# soth-core.net
KiCad netlist of a schematic drawn in EAGLE
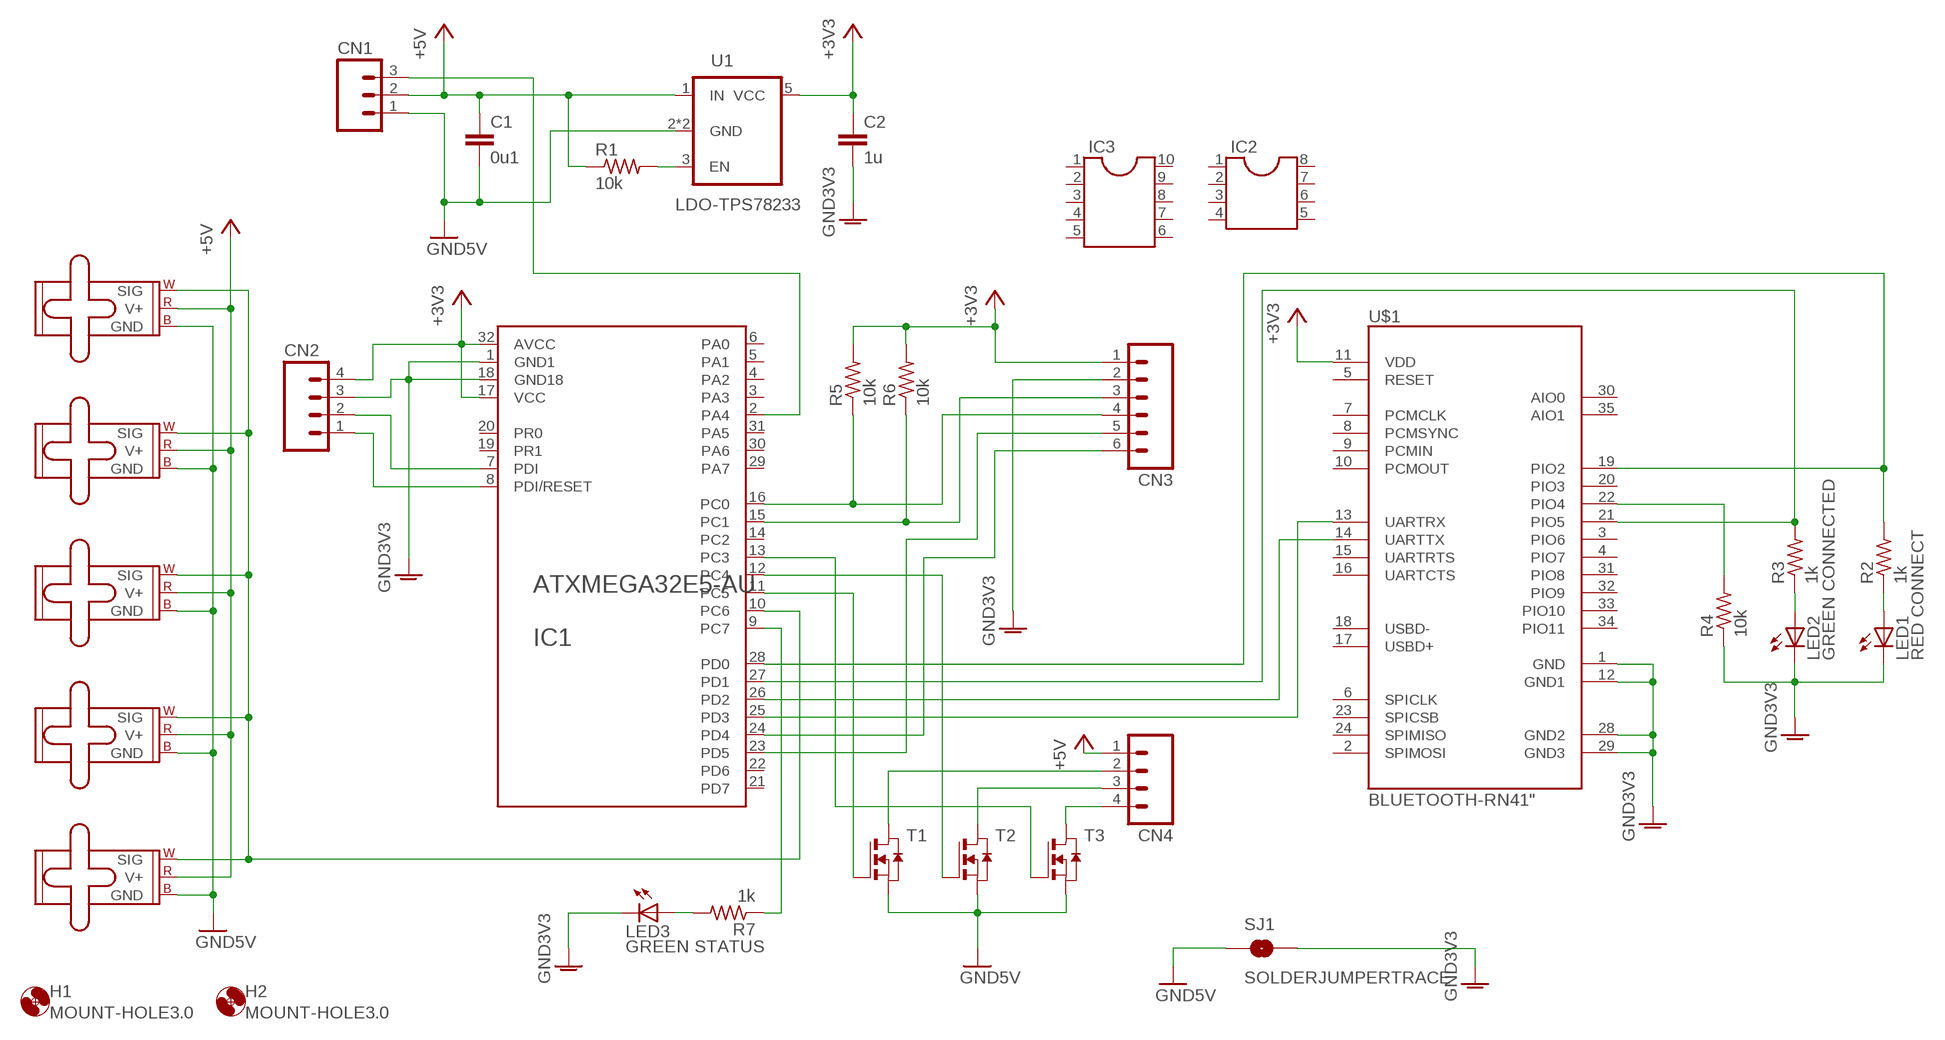
[diagram p0: schematic, sheet 1]

(export (version "E")
  (design (tool "Eeschema 10.0.6"))
  (components
    (comp (ref "C1")
      (value "0u1")
      (footprint "eagle-import:C1608")
      (libsource (lib "eagle-import") (part "C-EUC1608"))
    )
    (comp (ref "C2")
      (value "1u")
      (footprint "eagle-import:C1608")
      (libsource (lib "eagle-import") (part "C-EUC1608"))
    )
    (comp (ref "CN1")
      (value "M03PTH")
      (footprint "eagle-import:1X03")
      (libsource (lib "eagle-import") (part "M03PTH"))
    )
    (comp (ref "CN2")
      (value "M04PTH")
      (footprint "eagle-import:1X04")
      (libsource (lib "eagle-import") (part "M04PTH"))
    )
    (comp (ref "CN3")
      (value "M06SILK_FEMALE_PTH")
      (footprint "eagle-import:1X06")
      (libsource (lib "eagle-import") (part "M06SILK_FEMALE_PTH"))
    )
    (comp (ref "CN4")
      (value "M04PTH")
      (footprint "eagle-import:1X04")
      (libsource (lib "eagle-import") (part "M04PTH"))
    )
    (comp (ref "H1")
      (value "MOUNT-HOLE3.0")
      (footprint "eagle-import:3,0")
      (libsource (lib "eagle-import") (part "MOUNT-HOLE3.0"))
    )
    (comp (ref "H2")
      (value "MOUNT-HOLE3.0")
      (footprint "eagle-import:3,0")
      (libsource (lib "eagle-import") (part "MOUNT-HOLE3.0"))
    )
    (comp (ref "IC1")
      (value "ATXMEGA32E5-AU")
      (footprint "eagle-import:TQFP32-08")
      (libsource (lib "eagle-import") (part "ATXMEGA32E5/16E5/8E5ATXMEGA32E5-AU"))
    )
    (comp (ref "IC2")
      (value "DIL8")
      (footprint "eagle-import:DIL08")
      (libsource (lib "eagle-import") (part "DIL8"))
    )
    (comp (ref "IC3")
      (value "DIL10")
      (footprint "eagle-import:DIL10")
      (libsource (lib "eagle-import") (part "DIL10"))
    )
    (comp (ref "LED1")
      (value "RED CONNECT")
      (footprint "eagle-import:CHIPLED_1206")
      (libsource (lib "eagle-import") (part "LEDCHIPLED_1206"))
    )
    (comp (ref "LED2")
      (value "GREEN CONNECTED")
      (footprint "eagle-import:CHIPLED_1206")
      (libsource (lib "eagle-import") (part "LEDCHIPLED_1206"))
    )
    (comp (ref "LED3")
      (value "GREEN STATUS")
      (footprint "eagle-import:CHIPLED_1206")
      (libsource (lib "eagle-import") (part "LEDCHIPLED_1206"))
    )
    (comp (ref "M1")
      (value "SMALL_SERVO")
      (footprint "eagle-import:1X03")
      (libsource (lib "eagle-import") (part "SMALL_SERVO"))
    )
    (comp (ref "M2")
      (value "SMALL_SERVO")
      (footprint "eagle-import:1X03")
      (libsource (lib "eagle-import") (part "SMALL_SERVO"))
    )
    (comp (ref "M3")
      (value "SMALL_SERVO")
      (footprint "eagle-import:1X03")
      (libsource (lib "eagle-import") (part "SMALL_SERVO"))
    )
    (comp (ref "M4")
      (value "SMALL_SERVO")
      (footprint "eagle-import:1X03")
      (libsource (lib "eagle-import") (part "SMALL_SERVO"))
    )
    (comp (ref "M5")
      (value "SMALL_SERVO")
      (footprint "eagle-import:1X03")
      (libsource (lib "eagle-import") (part "SMALL_SERVO"))
    )
    (comp (ref "R1")
      (value "10k")
      (footprint "eagle-import:R0603")
      (libsource (lib "eagle-import") (part "R-US_R0603"))
    )
    (comp (ref "R2")
      (value "1k")
      (footprint "eagle-import:R0603")
      (libsource (lib "eagle-import") (part "R-US_R0603"))
    )
    (comp (ref "R3")
      (value "1k")
      (footprint "eagle-import:R0603")
      (libsource (lib "eagle-import") (part "R-US_R0603"))
    )
    (comp (ref "R4")
      (value "10k")
      (footprint "eagle-import:R0603")
      (libsource (lib "eagle-import") (part "R-US_R0603"))
    )
    (comp (ref "R5")
      (value "10k")
      (footprint "eagle-import:R0603")
      (libsource (lib "eagle-import") (part "R-US_R0603"))
    )
    (comp (ref "R6")
      (value "10k")
      (footprint "eagle-import:R0603")
      (libsource (lib "eagle-import") (part "R-US_R0603"))
    )
    (comp (ref "R7")
      (value "1k")
      (footprint "eagle-import:R0603")
      (libsource (lib "eagle-import") (part "R-US_R0603"))
    )
    (comp (ref "SJ1")
      (value "SOLDERJUMPERTRACE")
      (footprint "eagle-import:SJ_2S-TRACE")
      (libsource (lib "eagle-import") (part "SOLDERJUMPERTRACE"))
    )
    (comp (ref "T1")
      (value "NMOSSOT23")
      (footprint "eagle-import:SOT-23")
      (libsource (lib "eagle-import") (part "NMOSSOT23"))
    )
    (comp (ref "T2")
      (value "NMOSSOT23")
      (footprint "eagle-import:SOT-23")
      (libsource (lib "eagle-import") (part "NMOSSOT23"))
    )
    (comp (ref "T3")
      (value "NMOSSOT23")
      (footprint "eagle-import:SOT-23")
      (libsource (lib "eagle-import") (part "NMOSSOT23"))
    )
    (comp (ref "U$1")
      (value "BLUETOOTH-RN41\"")
      (footprint "eagle-import:RN41")
      (libsource (lib "eagle-import") (part "BLUETOOTH-RN41{dblquote}"))
    )
    (comp (ref "U1")
      (value "LDO-TPS78233")
      (footprint "eagle-import:SOT23-5")
      (libsource (lib "eagle-import") (part "LDO-TPS78233"))
    )
  )
  (nets
    (net (code "1") (name "+3V3") (class "Default")
      (node (ref "C2") (pin "1") (pinfunction "1_1") (pintype "passive"))
      (node (ref "CN2") (pin "4") (pinfunction "4_4") (pintype "passive"))
      (node (ref "CN3") (pin "1") (pinfunction "1_1") (pintype "passive"))
      (node (ref "IC1") (pin "17") (pinfunction "VCC_17") (pintype "power_in"))
      (node (ref "IC1") (pin "32") (pinfunction "AVCC_32") (pintype "power_in"))
      (node (ref "R5") (pin "2") (pinfunction "2_2") (pintype "passive"))
      (node (ref "R6") (pin "2") (pinfunction "2_2") (pintype "passive"))
      (node (ref "U$1") (pin "11") (pinfunction "VDD_11") (pintype "bidirectional"))
      (node (ref "U1") (pin "5") (pinfunction "VCC_5") (pintype "power_in"))
    )
    (net (code "2") (name "+5V") (class "Default")
      (node (ref "C1") (pin "1") (pinfunction "1_1") (pintype "passive"))
      (node (ref "CN1") (pin "2") (pinfunction "2_2") (pintype "passive"))
      (node (ref "CN4") (pin "1") (pinfunction "1_1") (pintype "passive"))
      (node (ref "M1") (pin "2") (pinfunction "V+_2") (pintype "bidirectional"))
      (node (ref "M2") (pin "2") (pinfunction "V+_2") (pintype "bidirectional"))
      (node (ref "M3") (pin "2") (pinfunction "V+_2") (pintype "bidirectional"))
      (node (ref "M4") (pin "2") (pinfunction "V+_2") (pintype "bidirectional"))
      (node (ref "M5") (pin "2") (pinfunction "V+_2") (pintype "bidirectional"))
      (node (ref "R1") (pin "1") (pinfunction "1_1") (pintype "passive"))
      (node (ref "U1") (pin "1") (pinfunction "IN_1") (pintype "input"))
    )
    (net (code "3") (name "GND3V3") (class "Default")
      (node (ref "C2") (pin "2") (pinfunction "2_2") (pintype "passive"))
      (node (ref "CN2") (pin "3") (pinfunction "3_3") (pintype "passive"))
      (node (ref "CN3") (pin "2") (pinfunction "2_2") (pintype "passive"))
      (node (ref "IC1") (pin "1") (pinfunction "GND1_1") (pintype "power_in"))
      (node (ref "IC1") (pin "18") (pinfunction "GND18_18") (pintype "power_in"))
      (node (ref "LED1") (pin "C") (pinfunction "C_C") (pintype "passive"))
      (node (ref "LED2") (pin "C") (pinfunction "C_C") (pintype "passive"))
      (node (ref "LED3") (pin "C") (pinfunction "C_C") (pintype "passive"))
      (node (ref "R4") (pin "1") (pinfunction "1_1") (pintype "passive"))
      (node (ref "SJ1") (pin "2") (pinfunction "2_2") (pintype "passive"))
      (node (ref "U$1") (pin "1") (pinfunction "GND_1") (pintype "bidirectional"))
      (node (ref "U$1") (pin "12") (pinfunction "GND1_12") (pintype "bidirectional"))
      (node (ref "U$1") (pin "28") (pinfunction "GND2_28") (pintype "bidirectional"))
      (node (ref "U$1") (pin "29") (pinfunction "GND3_29") (pintype "bidirectional"))
    )
    (net (code "4") (name "GND5V") (class "Default")
      (node (ref "C1") (pin "2") (pinfunction "2_2") (pintype "passive"))
      (node (ref "CN1") (pin "1") (pinfunction "1_1") (pintype "passive"))
      (node (ref "M1") (pin "3") (pinfunction "GND_3") (pintype "bidirectional"))
      (node (ref "M2") (pin "3") (pinfunction "GND_3") (pintype "bidirectional"))
      (node (ref "M3") (pin "3") (pinfunction "GND_3") (pintype "bidirectional"))
      (node (ref "M4") (pin "3") (pinfunction "GND_3") (pintype "bidirectional"))
      (node (ref "M5") (pin "3") (pinfunction "GND_3") (pintype "bidirectional"))
      (node (ref "SJ1") (pin "1") (pinfunction "1_1") (pintype "passive"))
      (node (ref "T1") (pin "2") (pinfunction "S_2") (pintype "passive"))
      (node (ref "T2") (pin "2") (pinfunction "S_2") (pintype "passive"))
      (node (ref "T3") (pin "2") (pinfunction "S_2") (pintype "passive"))
      (node (ref "U1") (pin "2") (pinfunction "GND_2") (pintype "input"))
      (node (ref "U1") (pin "4") (pinfunction "GND_4") (pintype "input"))
    )
    (net (code "5") (name "Net-(IC1-PA4)") (class "Default")
      (node (ref "CN1") (pin "3") (pinfunction "3_3") (pintype "passive"))
      (node (ref "IC1") (pin "2") (pinfunction "PA4_2") (pintype "bidirectional"))
    )
    (net (code "6") (name "Net-(IC1-PC0)") (class "Default")
      (node (ref "CN3") (pin "4") (pinfunction "4_4") (pintype "passive"))
      (node (ref "IC1") (pin "16") (pinfunction "PC0_16") (pintype "bidirectional"))
      (node (ref "R5") (pin "1") (pinfunction "1_1") (pintype "passive"))
    )
    (net (code "7") (name "Net-(IC1-PC1)") (class "Default")
      (node (ref "CN3") (pin "3") (pinfunction "3_3") (pintype "passive"))
      (node (ref "IC1") (pin "15") (pinfunction "PC1_15") (pintype "bidirectional"))
      (node (ref "R6") (pin "1") (pinfunction "1_1") (pintype "passive"))
    )
    (net (code "8") (name "Net-(IC1-PC3)") (class "Default")
      (node (ref "IC1") (pin "13") (pinfunction "PC3_13") (pintype "bidirectional"))
      (node (ref "T3") (pin "3") (pinfunction "G_3") (pintype "passive"))
    )
    (net (code "9") (name "Net-(IC1-PC4)") (class "Default")
      (node (ref "IC1") (pin "12") (pinfunction "PC4_12") (pintype "bidirectional"))
      (node (ref "T2") (pin "3") (pinfunction "G_3") (pintype "passive"))
    )
    (net (code "10") (name "Net-(IC1-PC5)") (class "Default")
      (node (ref "IC1") (pin "11") (pinfunction "PC5_11") (pintype "bidirectional"))
      (node (ref "T1") (pin "3") (pinfunction "G_3") (pintype "passive"))
    )
    (net (code "11") (name "Net-(IC1-PC6)") (class "Default")
      (node (ref "IC1") (pin "10") (pinfunction "PC6_10") (pintype "bidirectional"))
      (node (ref "M1") (pin "1") (pinfunction "SIG_1") (pintype "bidirectional"))
      (node (ref "M2") (pin "1") (pinfunction "SIG_1") (pintype "bidirectional"))
      (node (ref "M3") (pin "1") (pinfunction "SIG_1") (pintype "bidirectional"))
      (node (ref "M4") (pin "1") (pinfunction "SIG_1") (pintype "bidirectional"))
      (node (ref "M5") (pin "1") (pinfunction "SIG_1") (pintype "bidirectional"))
    )
    (net (code "12") (name "Net-(IC1-PC7)") (class "Default")
      (node (ref "IC1") (pin "9") (pinfunction "PC7_9") (pintype "bidirectional"))
      (node (ref "R7") (pin "1") (pinfunction "1_1") (pintype "passive"))
    )
    (net (code "13") (name "Net-(IC1-PD0)") (class "Default")
      (node (ref "IC1") (pin "28") (pinfunction "PD0_28") (pintype "bidirectional"))
      (node (ref "R2") (pin "2") (pinfunction "2_2") (pintype "passive"))
      (node (ref "U$1") (pin "19") (pinfunction "PIO2_19") (pintype "bidirectional"))
    )
    (net (code "14") (name "Net-(IC1-PD1)") (class "Default")
      (node (ref "IC1") (pin "27") (pinfunction "PD1_27") (pintype "bidirectional"))
      (node (ref "R3") (pin "2") (pinfunction "2_2") (pintype "passive"))
      (node (ref "U$1") (pin "21") (pinfunction "PIO5_21") (pintype "bidirectional"))
    )
    (net (code "15") (name "Net-(IC1-PD2)") (class "Default")
      (node (ref "IC1") (pin "26") (pinfunction "PD2_26") (pintype "bidirectional"))
      (node (ref "U$1") (pin "14") (pinfunction "UARTTX_14") (pintype "bidirectional"))
    )
    (net (code "16") (name "Net-(IC1-PD3)") (class "Default")
      (node (ref "IC1") (pin "25") (pinfunction "PD3_25") (pintype "bidirectional"))
      (node (ref "U$1") (pin "13") (pinfunction "UARTRX_13") (pintype "bidirectional"))
    )
    (net (code "17") (name "Net-(IC1-PD4)") (class "Default")
      (node (ref "CN3") (pin "6") (pinfunction "6_6") (pintype "passive"))
      (node (ref "IC1") (pin "24") (pinfunction "PD4_24") (pintype "bidirectional"))
    )
    (net (code "18") (name "Net-(IC1-PD5)") (class "Default")
      (node (ref "CN3") (pin "5") (pinfunction "5_5") (pintype "passive"))
      (node (ref "IC1") (pin "23") (pinfunction "PD5_23") (pintype "bidirectional"))
    )
    (net (code "19") (name "Net-(IC1-PDI)") (class "Default")
      (node (ref "CN2") (pin "2") (pinfunction "2_2") (pintype "passive"))
      (node (ref "IC1") (pin "7") (pinfunction "PDI_7") (pintype "bidirectional"))
    )
    (net (code "20") (name "Net-(IC1-PDI{slash}RESET)") (class "Default")
      (node (ref "CN2") (pin "1") (pinfunction "1_1") (pintype "passive"))
      (node (ref "IC1") (pin "8") (pinfunction "PDI/RESET_8") (pintype "bidirectional"))
    )
    (net (code "21") (name "Net-(LED1-PadA)") (class "Default")
      (node (ref "LED1") (pin "A") (pinfunction "A_A") (pintype "passive"))
      (node (ref "R2") (pin "1") (pinfunction "1_1") (pintype "passive"))
    )
    (net (code "22") (name "Net-(LED2-PadA)") (class "Default")
      (node (ref "LED2") (pin "A") (pinfunction "A_A") (pintype "passive"))
      (node (ref "R3") (pin "1") (pinfunction "1_1") (pintype "passive"))
    )
    (net (code "23") (name "Net-(LED3-PadA)") (class "Default")
      (node (ref "LED3") (pin "A") (pinfunction "A_A") (pintype "passive"))
      (node (ref "R7") (pin "2") (pinfunction "2_2") (pintype "passive"))
    )
    (net (code "24") (name "Net-(T1-D)") (class "Default")
      (node (ref "CN4") (pin "2") (pinfunction "2_2") (pintype "passive"))
      (node (ref "T1") (pin "1") (pinfunction "D_1") (pintype "passive"))
    )
    (net (code "25") (name "Net-(T2-D)") (class "Default")
      (node (ref "CN4") (pin "3") (pinfunction "3_3") (pintype "passive"))
      (node (ref "T2") (pin "1") (pinfunction "D_1") (pintype "passive"))
    )
    (net (code "26") (name "Net-(T3-D)") (class "Default")
      (node (ref "CN4") (pin "4") (pinfunction "4_4") (pintype "passive"))
      (node (ref "T3") (pin "1") (pinfunction "D_1") (pintype "passive"))
    )
    (net (code "27") (name "Net-(U$1-PIO4)") (class "Default")
      (node (ref "R4") (pin "2") (pinfunction "2_2") (pintype "passive"))
      (node (ref "U$1") (pin "22") (pinfunction "PIO4_22") (pintype "bidirectional"))
    )
    (net (code "28") (name "Net-(U1-EN)") (class "Default")
      (node (ref "R1") (pin "2") (pinfunction "2_2") (pintype "passive"))
      (node (ref "U1") (pin "3") (pinfunction "EN_3") (pintype "input"))
    )
    (net (code "29") (name "unconnected-(IC1-PA0-Pad6)") (class "Default")
      (node (ref "IC1") (pin "6") (pinfunction "PA0_6") (pintype "bidirectional"))
    )
    (net (code "30") (name "unconnected-(IC1-PA1-Pad5)") (class "Default")
      (node (ref "IC1") (pin "5") (pinfunction "PA1_5") (pintype "bidirectional"))
    )
    (net (code "31") (name "unconnected-(IC1-PA2-Pad4)") (class "Default")
      (node (ref "IC1") (pin "4") (pinfunction "PA2_4") (pintype "bidirectional"))
    )
    (net (code "32") (name "unconnected-(IC1-PA3-Pad3)") (class "Default")
      (node (ref "IC1") (pin "3") (pinfunction "PA3_3") (pintype "bidirectional"))
    )
    (net (code "33") (name "unconnected-(IC1-PA5-Pad31)") (class "Default")
      (node (ref "IC1") (pin "31") (pinfunction "PA5_31") (pintype "bidirectional"))
    )
    (net (code "34") (name "unconnected-(IC1-PA6-Pad30)") (class "Default")
      (node (ref "IC1") (pin "30") (pinfunction "PA6_30") (pintype "bidirectional"))
    )
    (net (code "35") (name "unconnected-(IC1-PA7-Pad29)") (class "Default")
      (node (ref "IC1") (pin "29") (pinfunction "PA7_29") (pintype "bidirectional"))
    )
    (net (code "36") (name "unconnected-(IC1-PC2-Pad14)") (class "Default")
      (node (ref "IC1") (pin "14") (pinfunction "PC2_14") (pintype "bidirectional"))
    )
    (net (code "37") (name "unconnected-(IC1-PD6-Pad22)") (class "Default")
      (node (ref "IC1") (pin "22") (pinfunction "PD6_22") (pintype "bidirectional"))
    )
    (net (code "38") (name "unconnected-(IC1-PD7-Pad21)") (class "Default")
      (node (ref "IC1") (pin "21") (pinfunction "PD7_21") (pintype "bidirectional"))
    )
    (net (code "39") (name "unconnected-(IC1-PR0-Pad20)") (class "Default")
      (node (ref "IC1") (pin "20") (pinfunction "PR0_20") (pintype "bidirectional"))
    )
    (net (code "40") (name "unconnected-(IC1-PR1-Pad19)") (class "Default")
      (node (ref "IC1") (pin "19") (pinfunction "PR1_19") (pintype "bidirectional"))
    )
    (net (code "41") (name "unconnected-(IC2-Pad1)") (class "Default")
      (node (ref "IC2") (pin "1") (pinfunction "1_1") (pintype "passive"))
    )
    (net (code "42") (name "unconnected-(IC2-Pad2)") (class "Default")
      (node (ref "IC2") (pin "2") (pinfunction "2_2") (pintype "passive"))
    )
    (net (code "43") (name "unconnected-(IC2-Pad3)") (class "Default")
      (node (ref "IC2") (pin "3") (pinfunction "3_3") (pintype "passive"))
    )
    (net (code "44") (name "unconnected-(IC2-Pad4)") (class "Default")
      (node (ref "IC2") (pin "4") (pinfunction "4_4") (pintype "passive"))
    )
    (net (code "45") (name "unconnected-(IC2-Pad5)") (class "Default")
      (node (ref "IC2") (pin "5") (pinfunction "5_5") (pintype "passive"))
    )
    (net (code "46") (name "unconnected-(IC2-Pad6)") (class "Default")
      (node (ref "IC2") (pin "6") (pinfunction "6_6") (pintype "passive"))
    )
    (net (code "47") (name "unconnected-(IC2-Pad7)") (class "Default")
      (node (ref "IC2") (pin "7") (pinfunction "7_7") (pintype "passive"))
    )
    (net (code "48") (name "unconnected-(IC2-Pad8)") (class "Default")
      (node (ref "IC2") (pin "8") (pinfunction "8_8") (pintype "passive"))
    )
    (net (code "49") (name "unconnected-(IC3-Pad1)") (class "Default")
      (node (ref "IC3") (pin "1") (pinfunction "1_1") (pintype "passive"))
    )
    (net (code "50") (name "unconnected-(IC3-Pad2)") (class "Default")
      (node (ref "IC3") (pin "2") (pinfunction "2_2") (pintype "passive"))
    )
    (net (code "51") (name "unconnected-(IC3-Pad3)") (class "Default")
      (node (ref "IC3") (pin "3") (pinfunction "3_3") (pintype "passive"))
    )
    (net (code "52") (name "unconnected-(IC3-Pad4)") (class "Default")
      (node (ref "IC3") (pin "4") (pinfunction "4_4") (pintype "passive"))
    )
    (net (code "53") (name "unconnected-(IC3-Pad5)") (class "Default")
      (node (ref "IC3") (pin "5") (pinfunction "5_5") (pintype "passive"))
    )
    (net (code "54") (name "unconnected-(IC3-Pad6)") (class "Default")
      (node (ref "IC3") (pin "6") (pinfunction "6_6") (pintype "passive"))
    )
    (net (code "55") (name "unconnected-(IC3-Pad7)") (class "Default")
      (node (ref "IC3") (pin "7") (pinfunction "7_7") (pintype "passive"))
    )
    (net (code "56") (name "unconnected-(IC3-Pad8)") (class "Default")
      (node (ref "IC3") (pin "8") (pinfunction "8_8") (pintype "passive"))
    )
    (net (code "57") (name "unconnected-(IC3-Pad9)") (class "Default")
      (node (ref "IC3") (pin "9") (pinfunction "9_9") (pintype "passive"))
    )
    (net (code "58") (name "unconnected-(IC3-Pad10)") (class "Default")
      (node (ref "IC3") (pin "10") (pinfunction "10_10") (pintype "passive"))
    )
    (net (code "59") (name "unconnected-(U$1-AIO0-Pad30)") (class "Default")
      (node (ref "U$1") (pin "30") (pinfunction "AIO0_30") (pintype "bidirectional"))
    )
    (net (code "60") (name "unconnected-(U$1-AIO1-Pad35)") (class "Default")
      (node (ref "U$1") (pin "35") (pinfunction "AIO1_35") (pintype "bidirectional"))
    )
    (net (code "61") (name "unconnected-(U$1-PCMCLK-Pad7)") (class "Default")
      (node (ref "U$1") (pin "7") (pinfunction "PCMCLK_7") (pintype "bidirectional"))
    )
    (net (code "62") (name "unconnected-(U$1-PCMIN-Pad9)") (class "Default")
      (node (ref "U$1") (pin "9") (pinfunction "PCMIN_9") (pintype "bidirectional"))
    )
    (net (code "63") (name "unconnected-(U$1-PCMOUT-Pad10)") (class "Default")
      (node (ref "U$1") (pin "10") (pinfunction "PCMOUT_10") (pintype "bidirectional"))
    )
    (net (code "64") (name "unconnected-(U$1-PCMSYNC-Pad8)") (class "Default")
      (node (ref "U$1") (pin "8") (pinfunction "PCMSYNC_8") (pintype "bidirectional"))
    )
    (net (code "65") (name "unconnected-(U$1-PIO3-Pad20)") (class "Default")
      (node (ref "U$1") (pin "20") (pinfunction "PIO3_20") (pintype "bidirectional"))
    )
    (net (code "66") (name "unconnected-(U$1-PIO6-Pad3)") (class "Default")
      (node (ref "U$1") (pin "3") (pinfunction "PIO6_3") (pintype "bidirectional"))
    )
    (net (code "67") (name "unconnected-(U$1-PIO7-Pad4)") (class "Default")
      (node (ref "U$1") (pin "4") (pinfunction "PIO7_4") (pintype "bidirectional"))
    )
    (net (code "68") (name "unconnected-(U$1-PIO8-Pad31)") (class "Default")
      (node (ref "U$1") (pin "31") (pinfunction "PIO8_31") (pintype "bidirectional"))
    )
    (net (code "69") (name "unconnected-(U$1-PIO9-Pad32)") (class "Default")
      (node (ref "U$1") (pin "32") (pinfunction "PIO9_32") (pintype "bidirectional"))
    )
    (net (code "70") (name "unconnected-(U$1-PIO10-Pad33)") (class "Default")
      (node (ref "U$1") (pin "33") (pinfunction "PIO10_33") (pintype "bidirectional"))
    )
    (net (code "71") (name "unconnected-(U$1-PIO11-Pad34)") (class "Default")
      (node (ref "U$1") (pin "34") (pinfunction "PIO11_34") (pintype "bidirectional"))
    )
    (net (code "72") (name "unconnected-(U$1-RESET-Pad5)") (class "Default")
      (node (ref "U$1") (pin "5") (pinfunction "RESET_5") (pintype "bidirectional"))
    )
    (net (code "73") (name "unconnected-(U$1-SPICLK-Pad6)") (class "Default")
      (node (ref "U$1") (pin "6") (pinfunction "SPICLK_6") (pintype "bidirectional"))
    )
    (net (code "74") (name "unconnected-(U$1-SPICSB-Pad23)") (class "Default")
      (node (ref "U$1") (pin "23") (pinfunction "SPICSB_23") (pintype "bidirectional"))
    )
    (net (code "75") (name "unconnected-(U$1-SPIMISO-Pad24)") (class "Default")
      (node (ref "U$1") (pin "24") (pinfunction "SPIMISO_24") (pintype "bidirectional"))
    )
    (net (code "76") (name "unconnected-(U$1-SPIMOSI-Pad2)") (class "Default")
      (node (ref "U$1") (pin "2") (pinfunction "SPIMOSI_2") (pintype "bidirectional"))
    )
    (net (code "77") (name "unconnected-(U$1-UARTCTS-Pad16)") (class "Default")
      (node (ref "U$1") (pin "16") (pinfunction "UARTCTS_16") (pintype "bidirectional"))
    )
    (net (code "78") (name "unconnected-(U$1-UARTRTS-Pad15)") (class "Default")
      (node (ref "U$1") (pin "15") (pinfunction "UARTRTS_15") (pintype "bidirectional"))
    )
    (net (code "79") (name "unconnected-(U$1-USBD+-Pad17)") (class "Default")
      (node (ref "U$1") (pin "17") (pinfunction "USBD+_17") (pintype "bidirectional"))
    )
    (net (code "80") (name "unconnected-(U$1-USBD--Pad18)") (class "Default")
      (node (ref "U$1") (pin "18") (pinfunction "USBD-_18") (pintype "bidirectional"))
    )
  )
)
